# ThirdStageAmplifier.net
KiCad netlist of a schematic drawn in Altium Designer
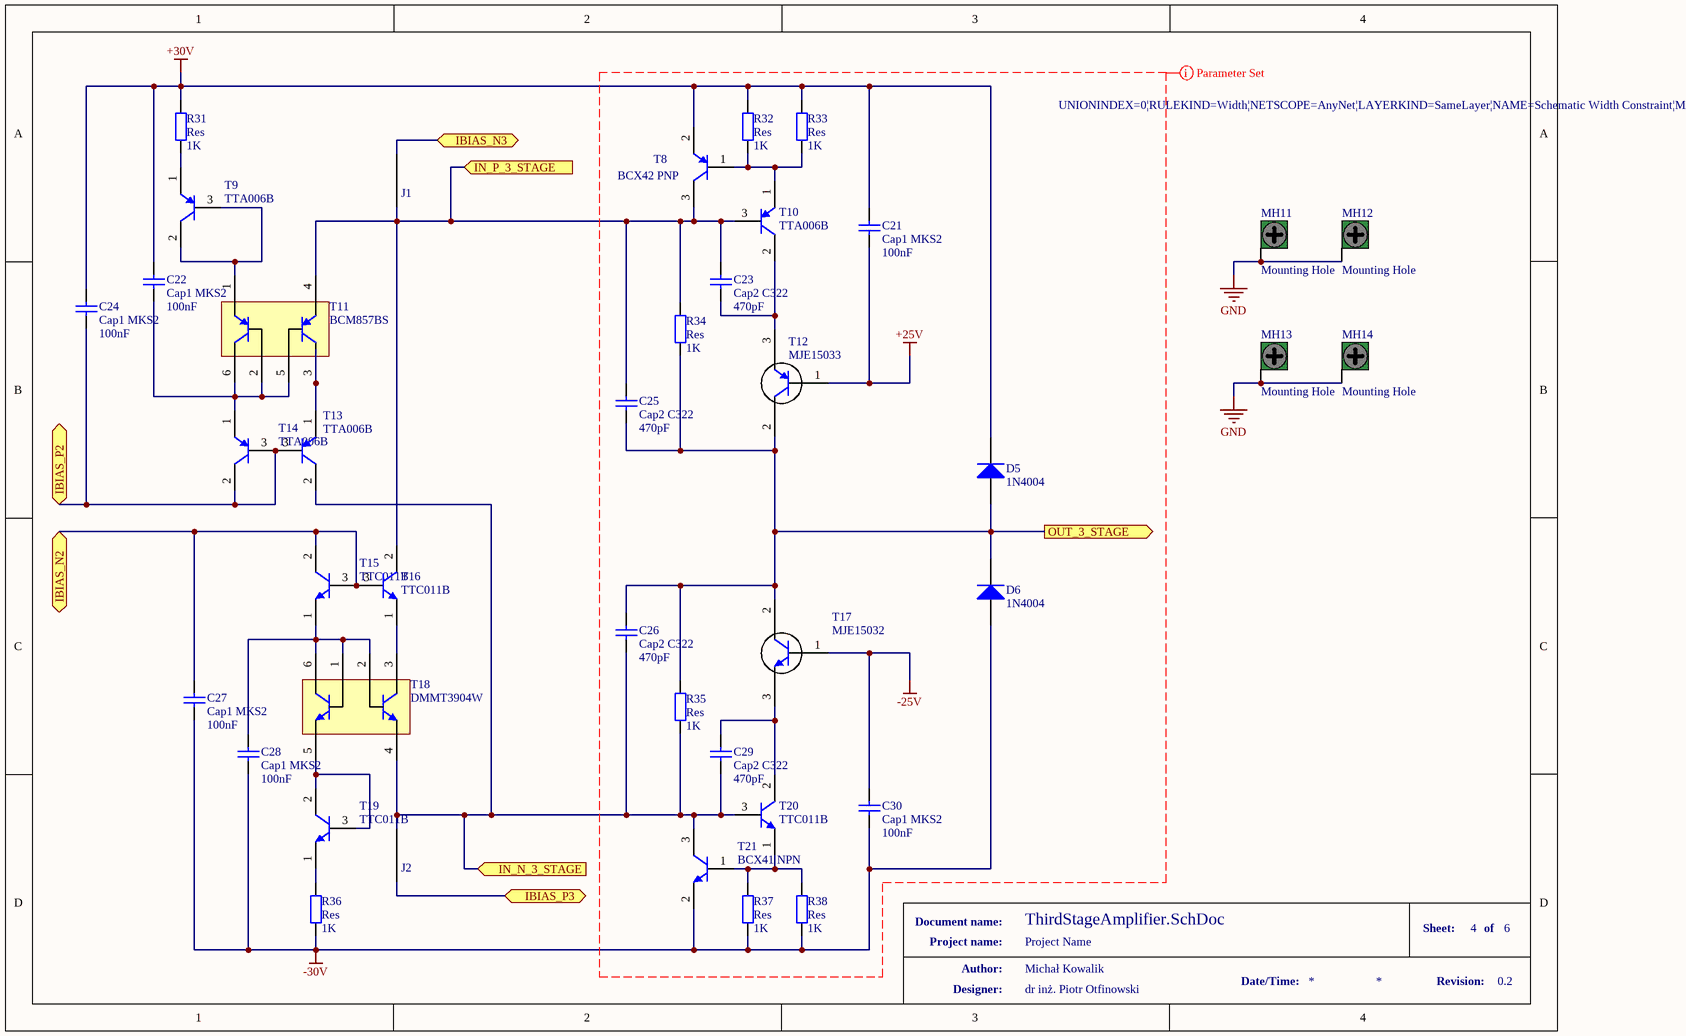
[diagram p0: ThirdStageAmplifier.SchDoc]

(export (version "E")
  (design (tool "Eeschema 10.0.6"))
  (components
    (comp (ref "C21")
      (value "Cap1 MKS2")
      (footprint "CAP-0.5-WIMA_MKS2")
      (description "WIMA MKS2 Metallized Polyester (PET) \r\nCapacitors in PCM 5 mm")
      (fields (field (name "ALTIUM_VALUE") "100nF"))
      (libsource (lib "SchematicLib") (part "Cap1"))
    )
    (comp (ref "C22")
      (value "Cap1 MKS2")
      (footprint "CAP-0.5-WIMA_MKS2")
      (description "WIMA MKS2 Metallized Polyester (PET) \r\nCapacitors in PCM 5 mm")
      (fields (field (name "ALTIUM_VALUE") "100nF"))
      (libsource (lib "SchematicLib") (part "Cap1"))
    )
    (comp (ref "C23")
      (value "Cap2 C322")
      (footprint "CAP-CERAMIC-200MIL")
      (fields (field (name "ALTIUM_VALUE") "470pF"))
      (libsource (lib "SchematicLib") (part "Cap2"))
    )
    (comp (ref "C24")
      (value "Cap1 MKS2")
      (footprint "CAP-0.5-WIMA_MKS2")
      (description "WIMA MKS2 Metallized Polyester (PET) \r\nCapacitors in PCM 5 mm")
      (fields (field (name "ALTIUM_VALUE") "100nF"))
      (libsource (lib "SchematicLib") (part "Cap1"))
    )
    (comp (ref "C25")
      (value "Cap2 C322")
      (footprint "CAP-CERAMIC-200MIL")
      (fields (field (name "ALTIUM_VALUE") "470pF"))
      (libsource (lib "SchematicLib") (part "Cap2"))
    )
    (comp (ref "C26")
      (value "Cap2 C322")
      (footprint "CAP-CERAMIC-200MIL")
      (fields (field (name "ALTIUM_VALUE") "470pF"))
      (libsource (lib "SchematicLib") (part "Cap2"))
    )
    (comp (ref "C27")
      (value "Cap1 MKS2")
      (footprint "CAP-0.5-WIMA_MKS2")
      (description "WIMA MKS2 Metallized Polyester (PET) \r\nCapacitors in PCM 5 mm")
      (fields (field (name "ALTIUM_VALUE") "100nF"))
      (libsource (lib "SchematicLib") (part "Cap1"))
    )
    (comp (ref "C28")
      (value "Cap1 MKS2")
      (footprint "CAP-0.5-WIMA_MKS2")
      (description "WIMA MKS2 Metallized Polyester (PET) \r\nCapacitors in PCM 5 mm")
      (fields (field (name "ALTIUM_VALUE") "100nF"))
      (libsource (lib "SchematicLib") (part "Cap1"))
    )
    (comp (ref "C29")
      (value "Cap2 C322")
      (footprint "CAP-CERAMIC-200MIL")
      (fields (field (name "ALTIUM_VALUE") "470pF"))
      (libsource (lib "SchematicLib") (part "Cap2"))
    )
    (comp (ref "C30")
      (value "Cap1 MKS2")
      (footprint "CAP-0.5-WIMA_MKS2")
      (description "WIMA MKS2 Metallized Polyester (PET) \r\nCapacitors in PCM 5 mm")
      (fields (field (name "ALTIUM_VALUE") "100nF"))
      (libsource (lib "SchematicLib") (part "Cap1"))
    )
    (comp (ref "D5")
      (value "1N4004")
      (footprint "DO-41")
      (description "Standard Recovery Rectifier Diodes")
      (libsource (lib "SchematicLib") (part "1N4004"))
    )
    (comp (ref "D6")
      (value "1N4004")
      (footprint "DO-41")
      (description "Standard Recovery Rectifier Diodes")
      (libsource (lib "SchematicLib") (part "1N4004"))
    )
    (comp (ref "J1")
      (value "NetTie")
      (footprint "NETTIE_20mil")
      (libsource (lib "SchematicLib") (part "NetTie"))
    )
    (comp (ref "J2")
      (value "NetTie")
      (footprint "NETTIE_20mil")
      (libsource (lib "SchematicLib") (part "NetTie"))
    )
    (comp (ref "MH11")
      (value "Mounting Hole")
      (footprint "agh_racing_2018:MOUNTING HOLE 3mm")
      (libsource (lib "SchematicLib") (part "Mounting Hole"))
    )
    (comp (ref "MH12")
      (value "Mounting Hole")
      (footprint "agh_racing_2018:MOUNTING HOLE 3mm")
      (libsource (lib "SchematicLib") (part "Mounting Hole"))
    )
    (comp (ref "MH13")
      (value "Mounting Hole")
      (footprint "agh_racing_2018:MOUNTING HOLE 3mm")
      (libsource (lib "SchematicLib") (part "Mounting Hole"))
    )
    (comp (ref "MH14")
      (value "Mounting Hole")
      (footprint "agh_racing_2018:MOUNTING HOLE 3mm")
      (libsource (lib "SchematicLib") (part "Mounting Hole"))
    )
    (comp (ref "R31")
      (value "Res")
      (footprint "RESISTOR-10mm")
      (description "Resistor")
      (fields (field (name "ALTIUM_VALUE") "1K"))
      (libsource (lib "SchematicLib") (part "Res"))
    )
    (comp (ref "R32")
      (value "Res")
      (footprint "RESISTOR-10mm")
      (description "Resistor")
      (fields (field (name "ALTIUM_VALUE") "1K"))
      (libsource (lib "SchematicLib") (part "Res"))
    )
    (comp (ref "R33")
      (value "Res")
      (footprint "RESISTOR-10mm")
      (description "Resistor")
      (fields (field (name "ALTIUM_VALUE") "1K"))
      (libsource (lib "SchematicLib") (part "Res"))
    )
    (comp (ref "R34")
      (value "Res")
      (footprint "RESISTOR-10mm")
      (description "Resistor")
      (fields (field (name "ALTIUM_VALUE") "1K"))
      (libsource (lib "SchematicLib") (part "Res"))
    )
    (comp (ref "R35")
      (value "Res")
      (footprint "RESISTOR-10mm")
      (description "Resistor")
      (fields (field (name "ALTIUM_VALUE") "1K"))
      (libsource (lib "SchematicLib") (part "Res"))
    )
    (comp (ref "R36")
      (value "Res")
      (footprint "RESISTOR-10mm")
      (description "Resistor")
      (fields (field (name "ALTIUM_VALUE") "1K"))
      (libsource (lib "SchematicLib") (part "Res"))
    )
    (comp (ref "R37")
      (value "Res")
      (footprint "RESISTOR-10mm")
      (description "Resistor")
      (fields (field (name "ALTIUM_VALUE") "1K"))
      (libsource (lib "SchematicLib") (part "Res"))
    )
    (comp (ref "R38")
      (value "Res")
      (footprint "RESISTOR-10mm")
      (description "Resistor")
      (fields (field (name "ALTIUM_VALUE") "1K"))
      (libsource (lib "SchematicLib") (part "Res"))
    )
    (comp (ref "T8")
      (value "BCX42 PNP")
      (footprint "SOT23_IPC_MD")
      (description "PNP Silicon AF and Switching Transistor")
      (libsource (lib "SchematicLib") (part "BCX42"))
    )
    (comp (ref "T9")
      (value "TTA006B")
      (footprint "TO-126")
      (description "PNP High Voltage Transistor")
      (libsource (lib "SchematicLib") (part "TTA006B"))
    )
    (comp (ref "T10")
      (value "TTA006B")
      (footprint "TO-126")
      (description "PNP High Voltage Transistor")
      (libsource (lib "SchematicLib") (part "TTA006B"))
    )
    (comp (ref "T11")
      (value "BCM857BS")
      (footprint "SOT363_IPC_MD")
      (description "40V MATCHED PAIR NPN SMALL SIGNAL TRANSISTOR")
      (libsource (lib "SchematicLib") (part "BCM857BS"))
    )
    (comp (ref "T12")
      (value "MJE15033")
      (footprint "TO-220")
      (description "PNP High Power Transistor")
      (libsource (lib "SchematicLib") (part "MJE15033"))
    )
    (comp (ref "T13")
      (value "TTA006B")
      (footprint "TO-126")
      (description "PNP High Voltage Transistor")
      (libsource (lib "SchematicLib") (part "TTA006B"))
    )
    (comp (ref "T14")
      (value "TTA006B")
      (footprint "TO-126")
      (description "PNP High Voltage Transistor")
      (libsource (lib "SchematicLib") (part "TTA006B"))
    )
    (comp (ref "T15")
      (value "TTC011B")
      (footprint "TO-126")
      (description "NPN High Voltage Transistor")
      (libsource (lib "SchematicLib") (part "TTC011B"))
    )
    (comp (ref "T16")
      (value "TTC011B")
      (footprint "TO-126")
      (description "NPN High Voltage Transistor")
      (libsource (lib "SchematicLib") (part "TTC011B"))
    )
    (comp (ref "T17")
      (value "MJE15032")
      (footprint "TO-220")
      (description "NPN High Power Transistor")
      (libsource (lib "SchematicLib") (part "MJE15032"))
    )
    (comp (ref "T18")
      (value "DMMT3904W")
      (footprint "SOT363_IPC_MD")
      (description "40V MATCHED PAIR NPN SMALL SIGNAL TRANSISTOR")
      (libsource (lib "SchematicLib") (part "DMMT3904W"))
    )
    (comp (ref "T19")
      (value "TTC011B")
      (footprint "TO-126")
      (description "NPN High Voltage Transistor")
      (libsource (lib "SchematicLib") (part "TTC011B"))
    )
    (comp (ref "T20")
      (value "TTC011B")
      (footprint "TO-126")
      (description "NPN High Voltage Transistor")
      (libsource (lib "SchematicLib") (part "TTC011B"))
    )
    (comp (ref "T21")
      (value "BCX41 NPN")
      (footprint "SOT23_IPC_MD")
      (description "NPN Silicon AF and Switching Transistor")
      (libsource (lib "SchematicLib") (part "BCX41"))
    )
  )
  (nets
    (net (code "1") (name "+25V") (class "Default")
      (node (ref "C21") (pin "1") (pinfunction "1_1") (pintype "passive"))
      (node (ref "T12") (pin "1") (pinfunction "B_1") (pintype "passive"))
    )
    (net (code "2") (name "+30V") (class "Default")
      (node (ref "C21") (pin "2") (pinfunction "2_2") (pintype "passive"))
      (node (ref "C22") (pin "2") (pinfunction "2_2") (pintype "passive"))
      (node (ref "C24") (pin "2") (pinfunction "2_2") (pintype "passive"))
      (node (ref "D5") (pin "2") (pinfunction "IN2_2") (pintype "passive"))
      (node (ref "R31") (pin "2") (pinfunction "2_2") (pintype "passive"))
      (node (ref "R32") (pin "2") (pinfunction "2_2") (pintype "passive"))
      (node (ref "R33") (pin "2") (pinfunction "2_2") (pintype "passive"))
      (node (ref "T8") (pin "2") (pinfunction "E_2") (pintype "passive"))
    )
    (net (code "3") (name "-25V") (class "Default")
      (node (ref "C30") (pin "2") (pinfunction "2_2") (pintype "passive"))
      (node (ref "T17") (pin "1") (pinfunction "B_1") (pintype "passive"))
    )
    (net (code "4") (name "-30V") (class "Default")
      (node (ref "C27") (pin "1") (pinfunction "1_1") (pintype "passive"))
      (node (ref "C28") (pin "1") (pinfunction "1_1") (pintype "passive"))
      (node (ref "C30") (pin "1") (pinfunction "1_1") (pintype "passive"))
      (node (ref "D6") (pin "1") (pinfunction "IN1_1") (pintype "passive"))
      (node (ref "R36") (pin "1") (pinfunction "1_1") (pintype "passive"))
      (node (ref "R37") (pin "1") (pinfunction "1_1") (pintype "passive"))
      (node (ref "R38") (pin "1") (pinfunction "1_1") (pintype "passive"))
      (node (ref "T21") (pin "2") (pinfunction "E_2") (pintype "passive"))
    )
    (net (code "5") (name "/IBIAS_N2") (class "Default")
      (node (ref "C27") (pin "2") (pinfunction "2_2") (pintype "passive"))
      (node (ref "T15") (pin "2") (pinfunction "C_2") (pintype "passive"))
      (node (ref "T15") (pin "3") (pinfunction "B_3") (pintype "passive"))
      (node (ref "T16") (pin "3") (pinfunction "B_3") (pintype "passive"))
    )
    (net (code "6") (name "/IBIAS_N3") (class "Default")
      (node (ref "J1") (pin "1") (pinfunction "1_1") (pintype "passive"))
    )
    (net (code "7") (name "/IBIAS_P2") (class "Default")
      (node (ref "C24") (pin "1") (pinfunction "1_1") (pintype "passive"))
      (node (ref "T13") (pin "3") (pinfunction "B_3") (pintype "passive"))
      (node (ref "T14") (pin "2") (pinfunction "C_2") (pintype "passive"))
      (node (ref "T14") (pin "3") (pinfunction "B_3") (pintype "passive"))
    )
    (net (code "8") (name "/IBIAS_P3") (class "Default")
      (node (ref "J2") (pin "1") (pinfunction "1_1") (pintype "passive"))
    )
    (net (code "9") (name "/IN_N_3_STAGE") (class "Default")
      (node (ref "C26") (pin "1") (pinfunction "1_1") (pintype "passive"))
      (node (ref "C29") (pin "1") (pinfunction "1_1") (pintype "passive"))
      (node (ref "J2") (pin "2") (pinfunction "2_2") (pintype "passive"))
      (node (ref "R35") (pin "1") (pinfunction "1_1") (pintype "passive"))
      (node (ref "T13") (pin "2") (pinfunction "C_2") (pintype "passive"))
      (node (ref "T18") (pin "4") (pinfunction "E2_4") (pintype "passive"))
      (node (ref "T20") (pin "3") (pinfunction "B_3") (pintype "passive"))
      (node (ref "T21") (pin "3") (pinfunction "C_3") (pintype "passive"))
    )
    (net (code "10") (name "/IN_P_3_STAGE") (class "Default")
      (node (ref "C23") (pin "2") (pinfunction "2_2") (pintype "passive"))
      (node (ref "C25") (pin "2") (pinfunction "2_2") (pintype "passive"))
      (node (ref "J1") (pin "2") (pinfunction "2_2") (pintype "passive"))
      (node (ref "R34") (pin "2") (pinfunction "2_2") (pintype "passive"))
      (node (ref "T10") (pin "3") (pinfunction "B_3") (pintype "passive"))
      (node (ref "T11") (pin "4") (pinfunction "C2_4") (pintype "passive"))
      (node (ref "T16") (pin "2") (pinfunction "C_2") (pintype "passive"))
      (node (ref "T8") (pin "3") (pinfunction "C_3") (pintype "passive"))
    )
    (net (code "11") (name "/OUT_3_STAGE") (class "Default")
      (node (ref "C25") (pin "1") (pinfunction "1_1") (pintype "passive"))
      (node (ref "C26") (pin "2") (pinfunction "2_2") (pintype "passive"))
      (node (ref "D5") (pin "1") (pinfunction "IN1_1") (pintype "passive"))
      (node (ref "D6") (pin "2") (pinfunction "IN2_2") (pintype "passive"))
      (node (ref "R34") (pin "1") (pinfunction "1_1") (pintype "passive"))
      (node (ref "R35") (pin "2") (pinfunction "2_2") (pintype "passive"))
      (node (ref "T12") (pin "2") (pinfunction "C_2") (pintype "passive"))
      (node (ref "T17") (pin "2") (pinfunction "C_2") (pintype "passive"))
    )
    (net (code "12") (name "GND") (class "Default")
      (node (ref "MH11") (pin "MOUNTING") (pinfunction "MOUNTING_MOUNTING") (pintype "passive"))
      (node (ref "MH12") (pin "MOUNTING") (pinfunction "MOUNTING_MOUNTING") (pintype "passive"))
      (node (ref "MH13") (pin "MOUNTING") (pinfunction "MOUNTING_MOUNTING") (pintype "passive"))
      (node (ref "MH14") (pin "MOUNTING") (pinfunction "MOUNTING_MOUNTING") (pintype "passive"))
    )
    (net (code "13") (name "Net-(T9-E)") (class "Default")
      (node (ref "R31") (pin "1") (pinfunction "1_1") (pintype "passive"))
      (node (ref "T9") (pin "1") (pinfunction "E_1") (pintype "passive"))
    )
    (net (code "14") (name "Net-(T10-C)") (class "Default")
      (node (ref "C23") (pin "1") (pinfunction "1_1") (pintype "passive"))
      (node (ref "T10") (pin "2") (pinfunction "C_2") (pintype "passive"))
      (node (ref "T12") (pin "3") (pinfunction "E_3") (pintype "passive"))
    )
    (net (code "15") (name "Net-(T10-E)") (class "Default")
      (node (ref "R32") (pin "1") (pinfunction "1_1") (pintype "passive"))
      (node (ref "R33") (pin "1") (pinfunction "1_1") (pintype "passive"))
      (node (ref "T10") (pin "1") (pinfunction "E_1") (pintype "passive"))
      (node (ref "T8") (pin "1") (pinfunction "B_1") (pintype "passive"))
    )
    (net (code "16") (name "Net-(T11-B1)") (class "Default")
      (node (ref "C22") (pin "1") (pinfunction "1_1") (pintype "passive"))
      (node (ref "T11") (pin "2") (pinfunction "B1_2") (pintype "passive"))
      (node (ref "T11") (pin "5") (pinfunction "B2_5") (pintype "passive"))
      (node (ref "T11") (pin "6") (pinfunction "E1_6") (pintype "passive"))
      (node (ref "T14") (pin "1") (pinfunction "E_1") (pintype "passive"))
    )
    (net (code "17") (name "Net-(T11-C1)") (class "Default")
      (node (ref "T11") (pin "1") (pinfunction "C1_1") (pintype "passive"))
      (node (ref "T9") (pin "2") (pinfunction "C_2") (pintype "passive"))
      (node (ref "T9") (pin "3") (pinfunction "B_3") (pintype "passive"))
    )
    (net (code "18") (name "Net-(T11-E2)") (class "Default")
      (node (ref "T11") (pin "3") (pinfunction "E2_3") (pintype "passive"))
      (node (ref "T13") (pin "1") (pinfunction "E_1") (pintype "passive"))
    )
    (net (code "19") (name "Net-(T15-E)") (class "Default")
      (node (ref "C28") (pin "2") (pinfunction "2_2") (pintype "passive"))
      (node (ref "T15") (pin "1") (pinfunction "E_1") (pintype "passive"))
      (node (ref "T18") (pin "1") (pinfunction "B1_1") (pintype "passive"))
      (node (ref "T18") (pin "2") (pinfunction "B2_2") (pintype "passive"))
      (node (ref "T18") (pin "6") (pinfunction "C1_6") (pintype "passive"))
    )
    (net (code "20") (name "Net-(T16-E)") (class "Default")
      (node (ref "T16") (pin "1") (pinfunction "E_1") (pintype "passive"))
      (node (ref "T18") (pin "3") (pinfunction "C2_3") (pintype "passive"))
    )
    (net (code "21") (name "Net-(T17-E)") (class "Default")
      (node (ref "C29") (pin "2") (pinfunction "2_2") (pintype "passive"))
      (node (ref "T17") (pin "3") (pinfunction "E_3") (pintype "passive"))
      (node (ref "T20") (pin "2") (pinfunction "C_2") (pintype "passive"))
    )
    (net (code "22") (name "Net-(T18-E1)") (class "Default")
      (node (ref "T18") (pin "5") (pinfunction "E1_5") (pintype "passive"))
      (node (ref "T19") (pin "2") (pinfunction "C_2") (pintype "passive"))
      (node (ref "T19") (pin "3") (pinfunction "B_3") (pintype "passive"))
    )
    (net (code "23") (name "Net-(T19-E)") (class "Default")
      (node (ref "R36") (pin "2") (pinfunction "2_2") (pintype "passive"))
      (node (ref "T19") (pin "1") (pinfunction "E_1") (pintype "passive"))
    )
    (net (code "24") (name "Net-(T20-E)") (class "Default")
      (node (ref "R37") (pin "2") (pinfunction "2_2") (pintype "passive"))
      (node (ref "R38") (pin "2") (pinfunction "2_2") (pintype "passive"))
      (node (ref "T20") (pin "1") (pinfunction "E_1") (pintype "passive"))
      (node (ref "T21") (pin "1") (pinfunction "B_1") (pintype "passive"))
    )
  )
)
